# flashlightbutton.net
KiCad netlist of a schematic drawn in EAGLE
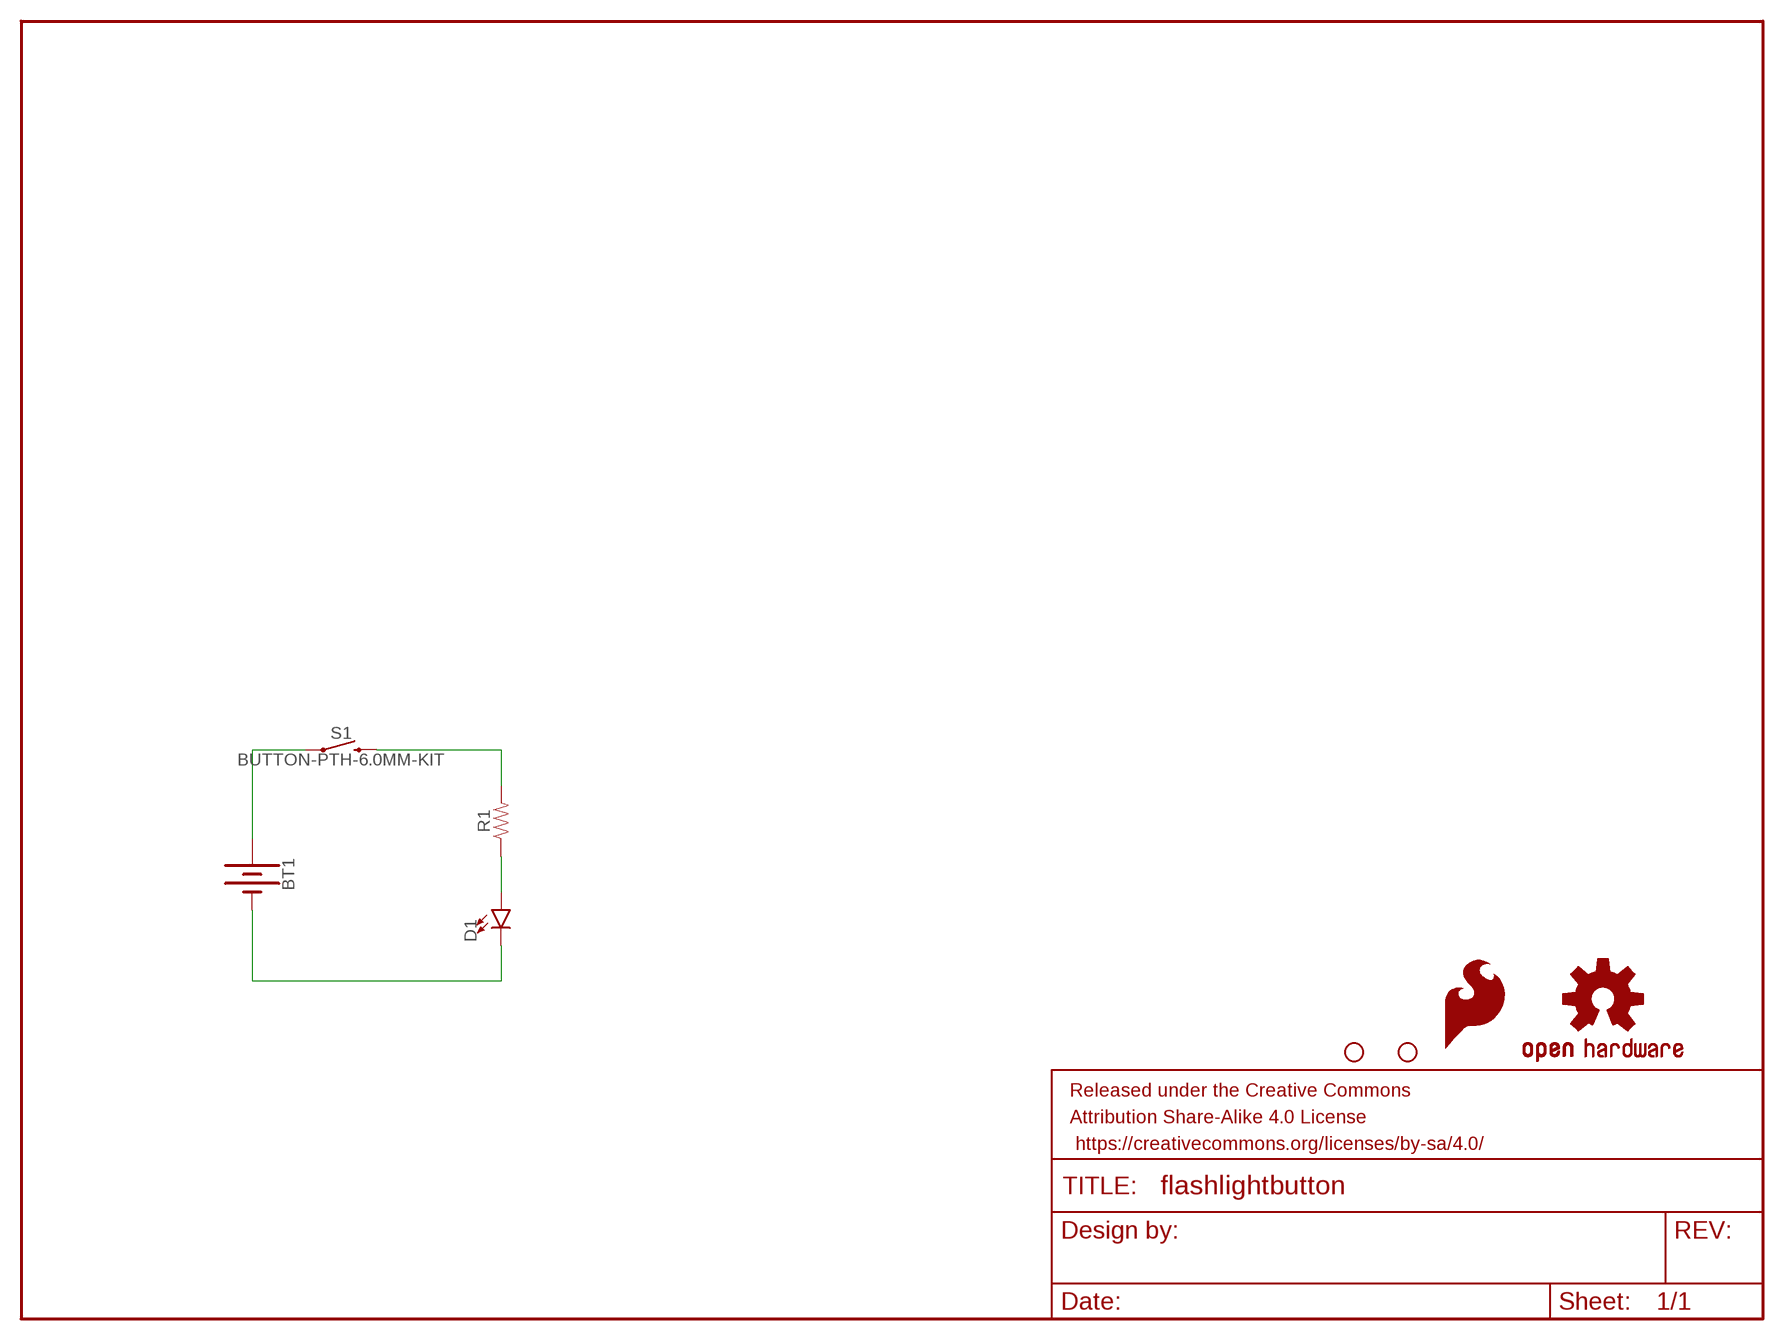
[diagram p0: schematic, sheet 1]

(export (version "E")
  (design (tool "Eeschema 10.0.6"))
  (components
    (comp (ref "BT1")
      (value "BATTERY-20MM_SMD")
      (footprint "eagle-import:BATTCON_20MM")
      (libsource (lib "eagle-import") (part "BATTERY-20MM_SMD"))
    )
    (comp (ref "D1")
      (value "LED5MM-KIT")
      (footprint "eagle-import:LED_5MM-KIT")
      (libsource (lib "eagle-import") (part "LED5MM-KIT"))
    )
    (comp (ref "FRAME1")
      (value "FRAME-LETTER")
      (footprint "eagle-import:CREATIVE_COMMONS")
      (libsource (lib "eagle-import") (part "FRAME-LETTER"))
    )
    (comp (ref "H1")
      (value "STAND-OFF")
      (footprint "eagle-import:STAND-OFF")
      (libsource (lib "eagle-import") (part "STAND-OFF"))
    )
    (comp (ref "H2")
      (value "STAND-OFF")
      (footprint "eagle-import:STAND-OFF")
      (libsource (lib "eagle-import") (part "STAND-OFF"))
    )
    (comp (ref "LOGO1")
      (value "OSHW-LOGOS")
      (footprint "eagle-import:OSHW-LOGO-S")
      (libsource (lib "eagle-import") (part "OSHW-LOGOS"))
    )
    (comp (ref "LOGO2")
      (value "SFE_LOGO_FLAME.1_INCH")
      (footprint "eagle-import:SFE_LOGO_FLAME_.1")
      (libsource (lib "eagle-import") (part "SFE_LOGO_FLAME.1_INCH"))
    )
    (comp (ref "R1")
      (value "RESISTORAXIAL-0.3-KIT")
      (footprint "eagle-import:AXIAL-0.3-KIT")
      (libsource (lib "eagle-import") (part "RESISTORAXIAL-0.3-KIT"))
    )
    (comp (ref "S1")
      (value "BUTTON-PTH-6.0MM-KIT")
      (footprint "eagle-import:TACTILE_SWITCH_PTH_6.0MM_KIT")
      (libsource (lib "eagle-import") (part "MOMENTARY-SWITCH-SPST-PTH-6.0MM-KIT"))
    )
  )
  (nets
    (net (code "1") (name "Net-(BT1-+)") (class "Default")
      (node (ref "BT1") (pin "1") (pinfunction "+_1") (pintype "power_in"))
      (node (ref "S1") (pin "1") (pinfunction "1_1") (pintype "passive"))
    )
    (net (code "2") (name "Net-(BT1--)") (class "Default")
      (node (ref "BT1") (pin "2") (pinfunction "-_2") (pintype "power_in"))
      (node (ref "D1") (pin "K") (pinfunction "C_K") (pintype "passive"))
    )
    (net (code "3") (name "Net-(R1-1)") (class "Default")
      (node (ref "D1") (pin "A") (pinfunction "A_A") (pintype "passive"))
      (node (ref "R1") (pin "P$1") (pinfunction "1_P$1") (pintype "passive"))
    )
    (net (code "4") (name "Net-(R1-2)") (class "Default")
      (node (ref "R1") (pin "P$2") (pinfunction "2_P$2") (pintype "passive"))
      (node (ref "S1") (pin "3") (pinfunction "2_3") (pintype "passive"))
    )
  )
)
